# CAP_TCH_4xBUT_CY8CMBR2044.net
KiCad netlist of a schematic drawn in Altium Designer
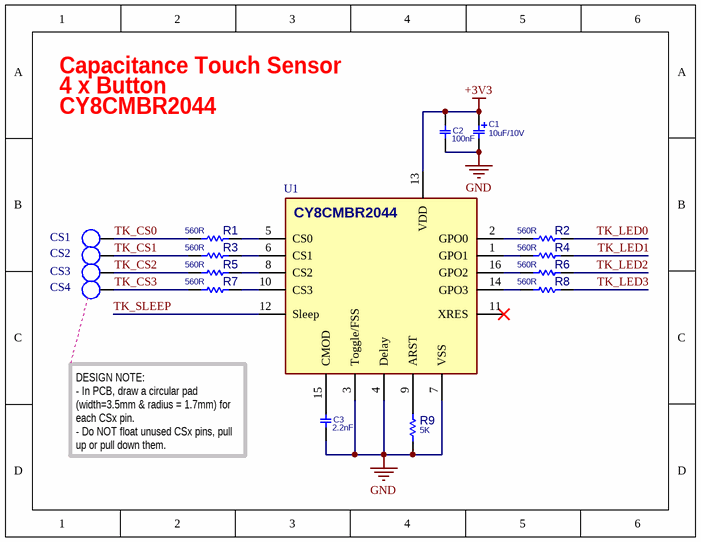
[diagram p0: CAP TCH 4xBUT CY8CMBR2044.SchDoc]

(export (version "E")
  (design (tool "Eeschema 10.0.6"))
  (components
    (comp (ref "C1")
      (value "10uF/10V")
      (footprint "C_TN_A")
      (description "CAP, SMD, TAN")
      (libsource (lib "PW Components 97_492") (part "CAP_SMD_TAN"))
    )
    (comp (ref "C2")
      (value "100nF")
      (footprint "C0603")
      (description "CAP, SMD, MLCC")
      (fields (field (name "MANF_P#") "MANF_PART#") (field (name "MANF") "Murata"))
      (libsource (lib "Passive") (part "CAP_SMD_MLCC"))
    )
    (comp (ref "C3")
      (value "2.2nF")
      (footprint "C0603")
      (description "CAP, SMD, MLCC")
      (fields (field (name "MANF_P#") "MANF_PART#") (field (name "MANF") "Murata"))
      (libsource (lib "Passive") (part "CAP_SMD_MLCC"))
    )
    (comp (ref "CS1")
      (value "CAP Sense")
      (footprint "CAP Sense 7mm")
      (libsource (lib "Button") (part "CAP Sense"))
    )
    (comp (ref "CS2")
      (value "CAP Sense")
      (footprint "CAP Sense 7mm")
      (libsource (lib "Button") (part "CAP Sense"))
    )
    (comp (ref "CS3")
      (value "CAP Sense")
      (footprint "CAP Sense 7mm")
      (libsource (lib "Button") (part "CAP Sense"))
    )
    (comp (ref "CS4")
      (value "CAP Sense")
      (footprint "CAP Sense 7mm")
      (libsource (lib "Button") (part "CAP Sense"))
    )
    (comp (ref "R1")
      (value "560R")
      (footprint "R0603")
      (description "RES, SMD")
      (fields (field (name "MANF_P#") "RK73H1ETTP4701F") (field (name "MANF") "KOA SPEER"))
      (libsource (lib "Passive") (part "RES_SMD"))
    )
    (comp (ref "R2")
      (value "560R")
      (footprint "R0603")
      (description "RES, SMD")
      (fields (field (name "MANF_P#") "RK73H1ETTP4701F") (field (name "MANF") "KOA SPEER"))
      (libsource (lib "Passive") (part "RES_SMD"))
    )
    (comp (ref "R3")
      (value "560R")
      (footprint "R0603")
      (description "RES, SMD")
      (fields (field (name "MANF_P#") "RK73H1ETTP4701F") (field (name "MANF") "KOA SPEER"))
      (libsource (lib "Passive") (part "RES_SMD"))
    )
    (comp (ref "R4")
      (value "560R")
      (footprint "R0603")
      (description "RES, SMD")
      (fields (field (name "MANF_P#") "RK73H1ETTP4701F") (field (name "MANF") "KOA SPEER"))
      (libsource (lib "Passive") (part "RES_SMD"))
    )
    (comp (ref "R5")
      (value "560R")
      (footprint "R0603")
      (description "RES, SMD")
      (fields (field (name "MANF_P#") "RK73H1ETTP4701F") (field (name "MANF") "KOA SPEER"))
      (libsource (lib "Passive") (part "RES_SMD"))
    )
    (comp (ref "R6")
      (value "560R")
      (footprint "R0603")
      (description "RES, SMD")
      (fields (field (name "MANF_P#") "RK73H1ETTP4701F") (field (name "MANF") "KOA SPEER"))
      (libsource (lib "Passive") (part "RES_SMD"))
    )
    (comp (ref "R7")
      (value "560R")
      (footprint "R0603")
      (description "RES, SMD")
      (fields (field (name "MANF_P#") "RK73H1ETTP4701F") (field (name "MANF") "KOA SPEER"))
      (libsource (lib "Passive") (part "RES_SMD"))
    )
    (comp (ref "R8")
      (value "560R")
      (footprint "R0603")
      (description "RES, SMD")
      (fields (field (name "MANF_P#") "RK73H1ETTP4701F") (field (name "MANF") "KOA SPEER"))
      (libsource (lib "Passive") (part "RES_SMD"))
    )
    (comp (ref "R9")
      (value "5K")
      (footprint "R0603")
      (description "RES, SMD")
      (fields (field (name "MANF_P#") "RK73H1ETTP4701F") (field (name "MANF") "KOA SPEER"))
      (libsource (lib "Passive") (part "RES_SMD"))
    )
    (comp (ref "U1")
      (value "CY8CMBR2044")
      (footprint "QFN50_16T_3X3")
      (description "CapTouchSensor, 4-CH, QFN16")
      (fields (field (name "MANF") "Microchip") (field (name "MANF_P#") "CAP1208-1-A4"))
      (libsource (lib "Capacitance Touch Sensor") (part "CY8CMBR2044_QFN16"))
    )
  )
  (nets
    (net (code "1") (name "+3V3") (class "Default")
      (node (ref "C1") (pin "1") (pinfunction "1_1") (pintype "passive"))
      (node (ref "C2") (pin "2") (pinfunction "2_2") (pintype "passive"))
      (node (ref "U1") (pin "13") (pinfunction "VDD_13") (pintype "passive"))
    )
    (net (code "2") (name "/TK_CS0") (class "Default")
      (node (ref "CS1") (pin "1") (pinfunction "1_1") (pintype "passive"))
      (node (ref "R1") (pin "1") (pinfunction "1_1") (pintype "passive"))
    )
    (net (code "3") (name "/TK_CS1") (class "Default")
      (node (ref "CS2") (pin "1") (pinfunction "1_1") (pintype "passive"))
      (node (ref "R3") (pin "1") (pinfunction "1_1") (pintype "passive"))
    )
    (net (code "4") (name "/TK_CS2") (class "Default")
      (node (ref "CS3") (pin "1") (pinfunction "1_1") (pintype "passive"))
      (node (ref "R5") (pin "1") (pinfunction "1_1") (pintype "passive"))
    )
    (net (code "5") (name "/TK_CS3") (class "Default")
      (node (ref "CS4") (pin "1") (pinfunction "1_1") (pintype "passive"))
      (node (ref "R7") (pin "1") (pinfunction "1_1") (pintype "passive"))
    )
    (net (code "6") (name "/TK_LED0") (class "Default")
      (node (ref "R2") (pin "2") (pinfunction "2_2") (pintype "passive"))
    )
    (net (code "7") (name "/TK_LED1") (class "Default")
      (node (ref "R4") (pin "2") (pinfunction "2_2") (pintype "passive"))
    )
    (net (code "8") (name "/TK_LED2") (class "Default")
      (node (ref "R6") (pin "2") (pinfunction "2_2") (pintype "passive"))
    )
    (net (code "9") (name "/TK_LED3") (class "Default")
      (node (ref "R8") (pin "2") (pinfunction "2_2") (pintype "passive"))
    )
    (net (code "10") (name "/TK_SLEEP") (class "Default")
      (node (ref "U1") (pin "12") (pinfunction "Sleep_12") (pintype "passive"))
    )
    (net (code "11") (name "GND") (class "Default")
      (node (ref "C1") (pin "2") (pinfunction "2_2") (pintype "passive"))
      (node (ref "C2") (pin "1") (pinfunction "1_1") (pintype "passive"))
      (node (ref "C3") (pin "1") (pinfunction "1_1") (pintype "passive"))
      (node (ref "R9") (pin "1") (pinfunction "1_1") (pintype "passive"))
      (node (ref "U1") (pin "3") (pinfunction "Toggle/FSS_3") (pintype "passive"))
      (node (ref "U1") (pin "4") (pinfunction "Delay_4") (pintype "passive"))
      (node (ref "U1") (pin "7") (pinfunction "VSS_7") (pintype "passive"))
    )
    (net (code "12") (name "Net-(U1-ARST)") (class "Default")
      (node (ref "R9") (pin "2") (pinfunction "2_2") (pintype "passive"))
      (node (ref "U1") (pin "9") (pinfunction "ARST_9") (pintype "passive"))
    )
    (net (code "13") (name "Net-(U1-CMOD)") (class "Default")
      (node (ref "C3") (pin "2") (pinfunction "2_2") (pintype "passive"))
      (node (ref "U1") (pin "15") (pinfunction "CMOD_15") (pintype "passive"))
    )
    (net (code "14") (name "Net-(U1-CS0)") (class "Default")
      (node (ref "R1") (pin "2") (pinfunction "2_2") (pintype "passive"))
      (node (ref "U1") (pin "5") (pinfunction "CS0_5") (pintype "passive"))
    )
    (net (code "15") (name "Net-(U1-CS1)") (class "Default")
      (node (ref "R3") (pin "2") (pinfunction "2_2") (pintype "passive"))
      (node (ref "U1") (pin "6") (pinfunction "CS1_6") (pintype "passive"))
    )
    (net (code "16") (name "Net-(U1-CS2)") (class "Default")
      (node (ref "R5") (pin "2") (pinfunction "2_2") (pintype "passive"))
      (node (ref "U1") (pin "8") (pinfunction "CS2_8") (pintype "passive"))
    )
    (net (code "17") (name "Net-(U1-CS3)") (class "Default")
      (node (ref "R7") (pin "2") (pinfunction "2_2") (pintype "passive"))
      (node (ref "U1") (pin "10") (pinfunction "CS3_10") (pintype "passive"))
    )
    (net (code "18") (name "Net-(U1-GPO0)") (class "Default")
      (node (ref "R2") (pin "1") (pinfunction "1_1") (pintype "passive"))
      (node (ref "U1") (pin "2") (pinfunction "GPO0_2") (pintype "passive"))
    )
    (net (code "19") (name "Net-(U1-GPO1)") (class "Default")
      (node (ref "R4") (pin "1") (pinfunction "1_1") (pintype "passive"))
      (node (ref "U1") (pin "1") (pinfunction "GPO1_1") (pintype "passive"))
    )
    (net (code "20") (name "Net-(U1-GPO2)") (class "Default")
      (node (ref "R6") (pin "1") (pinfunction "1_1") (pintype "passive"))
      (node (ref "U1") (pin "16") (pinfunction "GPO2_16") (pintype "passive"))
    )
    (net (code "21") (name "Net-(U1-GPO3)") (class "Default")
      (node (ref "R8") (pin "1") (pinfunction "1_1") (pintype "passive"))
      (node (ref "U1") (pin "14") (pinfunction "GPO3_14") (pintype "passive"))
    )
    (net (code "22") (name "unconnected-(U1-XRES-Pad11)") (class "Default")
      (node (ref "U1") (pin "11") (pinfunction "XRES_11") (pintype "passive+no_connect"))
    )
  )
)
